# Tractive_System_Active_Light_rev1.net
KiCad netlist of a schematic drawn in EAGLE
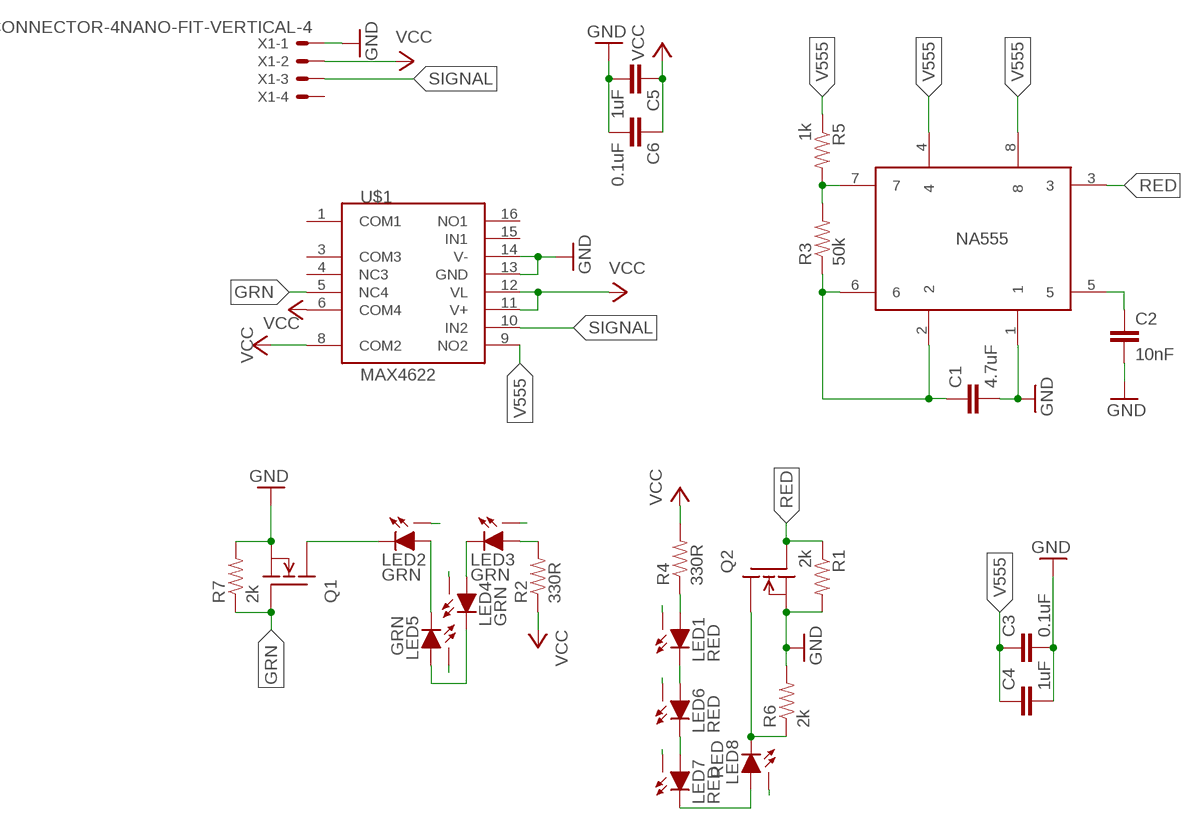
[diagram p0: schematic, sheet 1]

(export (version "E")
  (design (tool "Eeschema 10.0.6"))
  (components
    (comp (ref "C1")
      (value "4.7uF")
      (footprint "eagle-import:0603-CAP")
      (libsource (lib "eagle-import") (part "CAP0603-CAP"))
    )
    (comp (ref "C2")
      (value "10nF")
      (footprint "eagle-import:0603-CAP")
      (libsource (lib "eagle-import") (part "CAP0603-CAP"))
    )
    (comp (ref "C3")
      (value "0.1uF")
      (footprint "eagle-import:0603-CAP")
      (libsource (lib "eagle-import") (part "CAP0603-CAP"))
    )
    (comp (ref "C4")
      (value "1uF")
      (footprint "eagle-import:0603-CAP")
      (libsource (lib "eagle-import") (part "CAP0603-CAP"))
    )
    (comp (ref "C5")
      (value "1uF")
      (footprint "eagle-import:0603-CAP")
      (libsource (lib "eagle-import") (part "CAP0603-CAP"))
    )
    (comp (ref "C6")
      (value "0.1uF")
      (footprint "eagle-import:0603-CAP")
      (libsource (lib "eagle-import") (part "CAP0603-CAP"))
    )
    (comp (ref "LED1")
      (value "RED")
      (footprint "eagle-import:XP-E2")
      (libsource (lib "eagle-import") (part "XP-E2XP-E2"))
    )
    (comp (ref "LED2")
      (value "GRN")
      (footprint "eagle-import:XP-E2")
      (libsource (lib "eagle-import") (part "XP-E2XP-E2"))
    )
    (comp (ref "LED3")
      (value "GRN")
      (footprint "eagle-import:XP-E2")
      (libsource (lib "eagle-import") (part "XP-E2XP-E2"))
    )
    (comp (ref "LED4")
      (value "GRN")
      (footprint "eagle-import:XP-E2")
      (libsource (lib "eagle-import") (part "XP-E2XP-E2"))
    )
    (comp (ref "LED5")
      (value "GRN")
      (footprint "eagle-import:XP-E2")
      (libsource (lib "eagle-import") (part "XP-E2XP-E2"))
    )
    (comp (ref "LED6")
      (value "RED")
      (footprint "eagle-import:XP-E2")
      (libsource (lib "eagle-import") (part "XP-E2XP-E2"))
    )
    (comp (ref "LED7")
      (value "RED")
      (footprint "eagle-import:XP-E2")
      (libsource (lib "eagle-import") (part "XP-E2XP-E2"))
    )
    (comp (ref "LED8")
      (value "RED")
      (footprint "eagle-import:XP-E2")
      (libsource (lib "eagle-import") (part "XP-E2XP-E2"))
    )
    (comp (ref "NA555")
      (value "NA555SO-8")
      (footprint "eagle-import:SOIC-08")
      (libsource (lib "eagle-import") (part "NA555SO-8"))
    )
    (comp (ref "Q1")
      (value "DMG3406LSOT")
      (footprint "eagle-import:SOT23")
      (libsource (lib "eagle-import") (part "DMG3406LSOT"))
    )
    (comp (ref "Q2")
      (value "DMG3406LSOT")
      (footprint "eagle-import:SOT23")
      (libsource (lib "eagle-import") (part "DMG3406LSOT"))
    )
    (comp (ref "R1")
      (value "2k")
      (footprint "eagle-import:0603-RES")
      (libsource (lib "eagle-import") (part "RESISTOR0603-RES"))
    )
    (comp (ref "R2")
      (value "330R")
      (footprint "eagle-import:0603-RES")
      (libsource (lib "eagle-import") (part "RESISTOR0603-RES"))
    )
    (comp (ref "R3")
      (value "50k")
      (footprint "eagle-import:0603-RES")
      (libsource (lib "eagle-import") (part "RESISTOR0603-RES"))
    )
    (comp (ref "R4")
      (value "330R")
      (footprint "eagle-import:0603-RES")
      (libsource (lib "eagle-import") (part "RESISTOR0603-RES"))
    )
    (comp (ref "R5")
      (value "1k")
      (footprint "eagle-import:0603-RES")
      (libsource (lib "eagle-import") (part "RESISTOR0603-RES"))
    )
    (comp (ref "R6")
      (value "2k")
      (footprint "eagle-import:0603-RES")
      (libsource (lib "eagle-import") (part "RESISTOR0603-RES"))
    )
    (comp (ref "R7")
      (value "2k")
      (footprint "eagle-import:0603-RES")
      (libsource (lib "eagle-import") (part "RESISTOR0603-RES"))
    )
    (comp (ref "U$1")
      (value "MAX4622")
      (footprint "eagle-import:SO16")
      (libsource (lib "eagle-import") (part "MAX4622"))
    )
    (comp (ref "X1")
      (value "CONNECTOR-4NANO-FIT-VERTICAL-4")
      (footprint "eagle-import:NANO-FIT_VERTICAL-4")
      (libsource (lib "eagle-import") (part "CONNECTOR-4NANO-FIT-VERTICAL-4"))
    )
  )
  (nets
    (net (code "1") (name "GND") (class "Default")
      (node (ref "C1") (pin "2") (pinfunction "2_2") (pintype "passive"))
      (node (ref "C2") (pin "2") (pinfunction "2_2") (pintype "passive"))
      (node (ref "C3") (pin "2") (pinfunction "2_2") (pintype "passive"))
      (node (ref "C4") (pin "2") (pinfunction "2_2") (pintype "passive"))
      (node (ref "C5") (pin "2") (pinfunction "2_2") (pintype "passive"))
      (node (ref "C6") (pin "2") (pinfunction "2_2") (pintype "passive"))
      (node (ref "NA555") (pin "1") (pinfunction "1_1") (pintype "bidirectional"))
      (node (ref "Q1") (pin "2") (pinfunction "S_2") (pintype "passive"))
      (node (ref "Q2") (pin "2") (pinfunction "S_2") (pintype "passive"))
      (node (ref "R1") (pin "2") (pinfunction "2_2") (pintype "passive"))
      (node (ref "R6") (pin "2") (pinfunction "2_2") (pintype "passive"))
      (node (ref "R7") (pin "2") (pinfunction "2_2") (pintype "passive"))
      (node (ref "U$1") (pin "13") (pinfunction "GND_13") (pintype "bidirectional"))
      (node (ref "U$1") (pin "14") (pinfunction "V-_14") (pintype "bidirectional"))
      (node (ref "X1") (pin "P$1") (pinfunction "S_P$1") (pintype "passive"))
    )
    (net (code "2") (name "GRN") (class "Default")
      (node (ref "Q1") (pin "1") (pinfunction "G_1") (pintype "passive"))
      (node (ref "R7") (pin "1") (pinfunction "1_1") (pintype "passive"))
      (node (ref "U$1") (pin "5") (pinfunction "NC4_5") (pintype "bidirectional"))
    )
    (net (code "3") (name "Net-(C1-Pad1)") (class "Default")
      (node (ref "C1") (pin "1") (pinfunction "1_1") (pintype "passive"))
      (node (ref "NA555") (pin "2") (pinfunction "2_2") (pintype "bidirectional"))
      (node (ref "NA555") (pin "6") (pinfunction "6_6") (pintype "bidirectional"))
      (node (ref "R3") (pin "1") (pinfunction "1_1") (pintype "passive"))
    )
    (net (code "4") (name "Net-(C2-Pad1)") (class "Default")
      (node (ref "C2") (pin "1") (pinfunction "1_1") (pintype "passive"))
      (node (ref "NA555") (pin "5") (pinfunction "5_5") (pintype "bidirectional"))
    )
    (net (code "5") (name "Net-(LED1-PadA)") (class "Default")
      (node (ref "LED1") (pin "A") (pinfunction "A_A") (pintype "passive"))
      (node (ref "R4") (pin "1") (pinfunction "1_1") (pintype "passive"))
    )
    (net (code "6") (name "Net-(LED1-PadC)") (class "Default")
      (node (ref "LED1") (pin "C") (pinfunction "C_C") (pintype "passive"))
      (node (ref "LED6") (pin "A") (pinfunction "A_A") (pintype "passive"))
    )
    (net (code "7") (name "Net-(LED2-PadA)") (class "Default")
      (node (ref "LED2") (pin "A") (pinfunction "A_A") (pintype "passive"))
      (node (ref "LED5") (pin "C") (pinfunction "C_C") (pintype "passive"))
    )
    (net (code "8") (name "Net-(LED3-PadA)") (class "Default")
      (node (ref "LED3") (pin "A") (pinfunction "A_A") (pintype "passive"))
      (node (ref "R2") (pin "2") (pinfunction "2_2") (pintype "passive"))
    )
    (net (code "9") (name "Net-(LED3-PadC)") (class "Default")
      (node (ref "LED3") (pin "C") (pinfunction "C_C") (pintype "passive"))
      (node (ref "LED4") (pin "A") (pinfunction "A_A") (pintype "passive"))
    )
    (net (code "10") (name "Net-(LED4-PadC)") (class "Default")
      (node (ref "LED4") (pin "C") (pinfunction "C_C") (pintype "passive"))
      (node (ref "LED5") (pin "A") (pinfunction "A_A") (pintype "passive"))
    )
    (net (code "11") (name "Net-(LED6-PadC)") (class "Default")
      (node (ref "LED6") (pin "C") (pinfunction "C_C") (pintype "passive"))
      (node (ref "LED7") (pin "A") (pinfunction "A_A") (pintype "passive"))
    )
    (net (code "12") (name "Net-(LED7-PadC)") (class "Default")
      (node (ref "LED7") (pin "C") (pinfunction "C_C") (pintype "passive"))
      (node (ref "LED8") (pin "A") (pinfunction "A_A") (pintype "passive"))
    )
    (net (code "13") (name "Net-(NA555-Pad7)") (class "Default")
      (node (ref "NA555") (pin "7") (pinfunction "7_7") (pintype "bidirectional"))
      (node (ref "R3") (pin "2") (pinfunction "2_2") (pintype "passive"))
      (node (ref "R5") (pin "2") (pinfunction "2_2") (pintype "passive"))
    )
    (net (code "14") (name "Net-(Q1-D)") (class "Default")
      (node (ref "LED2") (pin "C") (pinfunction "C_C") (pintype "passive"))
      (node (ref "Q1") (pin "3") (pinfunction "D_3") (pintype "passive"))
    )
    (net (code "15") (name "Net-(Q2-D)") (class "Default")
      (node (ref "LED8") (pin "C") (pinfunction "C_C") (pintype "passive"))
      (node (ref "Q2") (pin "3") (pinfunction "D_3") (pintype "passive"))
      (node (ref "R6") (pin "1") (pinfunction "1_1") (pintype "passive"))
    )
    (net (code "16") (name "RED") (class "Default")
      (node (ref "NA555") (pin "3") (pinfunction "3_3") (pintype "bidirectional"))
      (node (ref "Q2") (pin "1") (pinfunction "G_1") (pintype "passive"))
      (node (ref "R1") (pin "1") (pinfunction "1_1") (pintype "passive"))
    )
    (net (code "17") (name "SIGNAL") (class "Default")
      (node (ref "U$1") (pin "10") (pinfunction "IN2_10") (pintype "bidirectional"))
      (node (ref "X1") (pin "P$3") (pinfunction "S_P$3") (pintype "passive"))
    )
    (net (code "18") (name "V555") (class "Default")
      (node (ref "C3") (pin "1") (pinfunction "1_1") (pintype "passive"))
      (node (ref "C4") (pin "1") (pinfunction "1_1") (pintype "passive"))
      (node (ref "NA555") (pin "4") (pinfunction "4_4") (pintype "bidirectional"))
      (node (ref "NA555") (pin "8") (pinfunction "8_8") (pintype "bidirectional"))
      (node (ref "R5") (pin "1") (pinfunction "1_1") (pintype "passive"))
      (node (ref "U$1") (pin "9") (pinfunction "NO2_9") (pintype "bidirectional"))
    )
    (net (code "19") (name "VCC") (class "Default")
      (node (ref "C5") (pin "1") (pinfunction "1_1") (pintype "passive"))
      (node (ref "C6") (pin "1") (pinfunction "1_1") (pintype "passive"))
      (node (ref "R2") (pin "1") (pinfunction "1_1") (pintype "passive"))
      (node (ref "R4") (pin "2") (pinfunction "2_2") (pintype "passive"))
      (node (ref "U$1") (pin "11") (pinfunction "V+_11") (pintype "bidirectional"))
      (node (ref "U$1") (pin "12") (pinfunction "VL_12") (pintype "bidirectional"))
      (node (ref "U$1") (pin "6") (pinfunction "COM4_6") (pintype "bidirectional"))
      (node (ref "U$1") (pin "8") (pinfunction "COM2_8") (pintype "bidirectional"))
      (node (ref "X1") (pin "P$2") (pinfunction "S_P$2") (pintype "passive"))
    )
    (net (code "20") (name "unconnected-(LED1-PadX)") (class "Default")
      (node (ref "LED1") (pin "X") (pinfunction "X_X") (pintype "passive"))
    )
    (net (code "21") (name "unconnected-(LED2-PadX)") (class "Default")
      (node (ref "LED2") (pin "X") (pinfunction "X_X") (pintype "passive"))
    )
    (net (code "22") (name "unconnected-(LED3-PadX)") (class "Default")
      (node (ref "LED3") (pin "X") (pinfunction "X_X") (pintype "passive"))
    )
    (net (code "23") (name "unconnected-(LED4-PadX)") (class "Default")
      (node (ref "LED4") (pin "X") (pinfunction "X_X") (pintype "passive"))
    )
    (net (code "24") (name "unconnected-(LED5-PadX)") (class "Default")
      (node (ref "LED5") (pin "X") (pinfunction "X_X") (pintype "passive"))
    )
    (net (code "25") (name "unconnected-(LED6-PadX)") (class "Default")
      (node (ref "LED6") (pin "X") (pinfunction "X_X") (pintype "passive"))
    )
    (net (code "26") (name "unconnected-(LED7-PadX)") (class "Default")
      (node (ref "LED7") (pin "X") (pinfunction "X_X") (pintype "passive"))
    )
    (net (code "27") (name "unconnected-(LED8-PadX)") (class "Default")
      (node (ref "LED8") (pin "X") (pinfunction "X_X") (pintype "passive"))
    )
    (net (code "28") (name "unconnected-(U$1-COM1-Pad1)") (class "Default")
      (node (ref "U$1") (pin "1") (pinfunction "COM1_1") (pintype "bidirectional"))
    )
    (net (code "29") (name "unconnected-(U$1-COM3-Pad3)") (class "Default")
      (node (ref "U$1") (pin "3") (pinfunction "COM3_3") (pintype "bidirectional"))
    )
    (net (code "30") (name "unconnected-(U$1-IN1-Pad15)") (class "Default")
      (node (ref "U$1") (pin "15") (pinfunction "IN1_15") (pintype "bidirectional"))
    )
    (net (code "31") (name "unconnected-(U$1-NC3-Pad4)") (class "Default")
      (node (ref "U$1") (pin "4") (pinfunction "NC3_4") (pintype "bidirectional"))
    )
    (net (code "32") (name "unconnected-(U$1-NO1-Pad16)") (class "Default")
      (node (ref "U$1") (pin "16") (pinfunction "NO1_16") (pintype "bidirectional"))
    )
    (net (code "33") (name "unconnected-(X1D-S-PadP$4)") (class "Default")
      (node (ref "X1") (pin "P$4") (pinfunction "S_P$4") (pintype "passive"))
    )
  )
)
